# Sheet1.net
KiCad netlist of a schematic drawn in Altium Designer
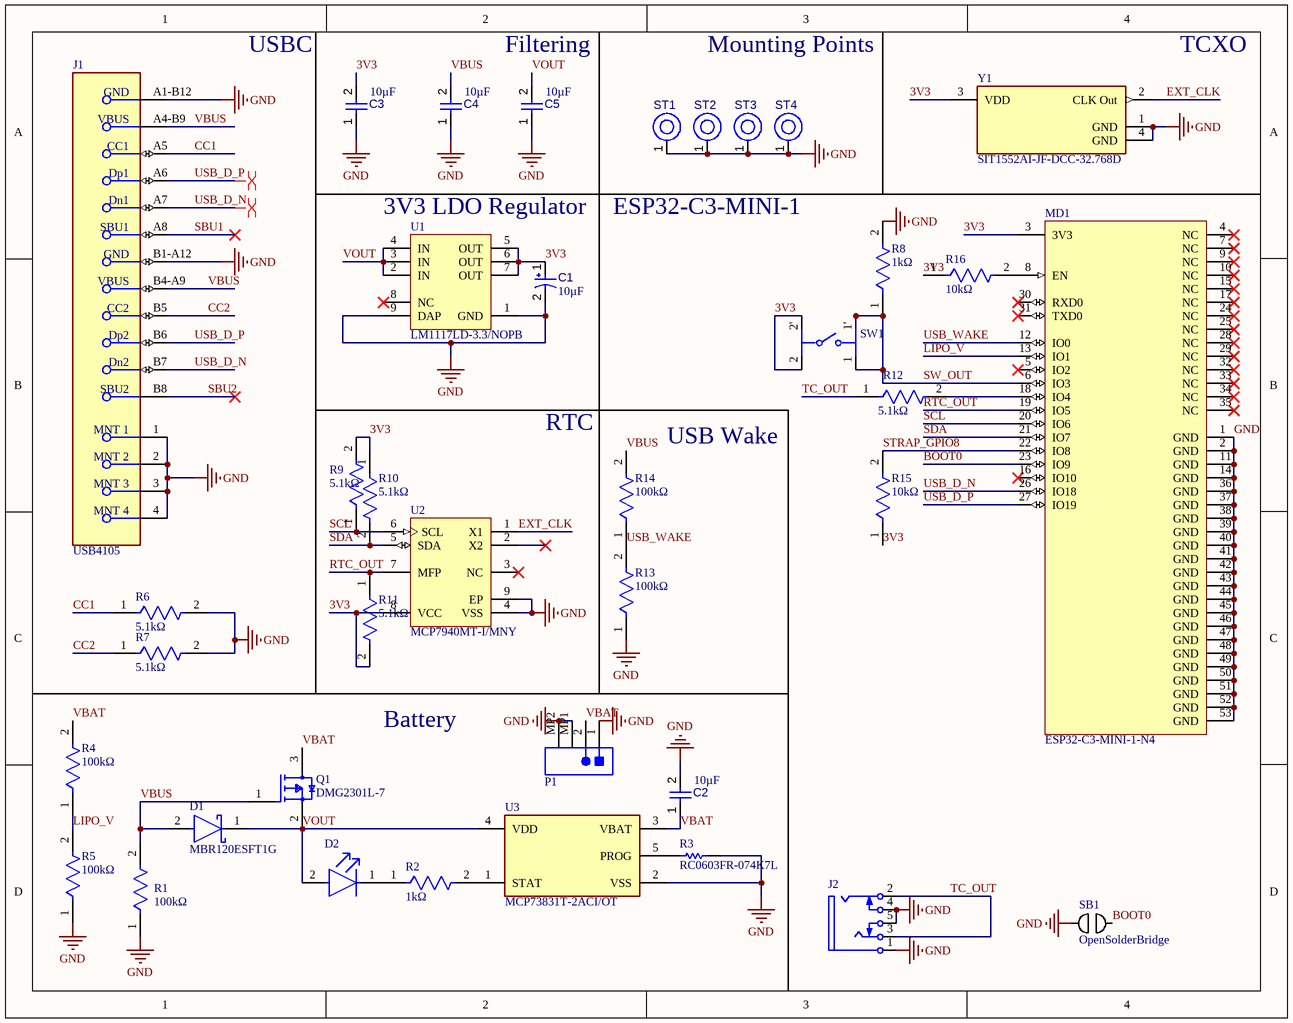
[diagram p0: Sheet1.SchDoc]

(export (version "E")
  (design (tool "Eeschema 10.0.6"))
  (components
    (comp (ref "C1")
      (value "10µF")
      (footprint "CAPMP3529X21-T_V")
      (description "Tantalum Capacitor, 10 uF, +/- 20%, 16 V, -55 to 125 degC, 1411 (3528 Metric), RoHS, Tape and Reel")
      (fields (field (name "TOLERANCE") "20%") (field (name "MANUFACTURER") "AVX Corporation"))
      (libsource (lib "Raleigh Slack") (part "CAP-P-2"))
    )
    (comp (ref "C2")
      (value "10µF")
      (footprint "CAPC0603(1608)100_L")
      (description "Chip Capacitor, 10µF +/-20%, 10V, 0603, Thickness 1 mm")
      (fields (field (name "TOLERANCE") "10%") (field (name "Comment") "Capacitor 10µF +/-20% 10V 0603"))
      (libsource (lib "Raleigh Slack") (part "CAP-NP-2"))
    )
    (comp (ref "C3")
      (value "10µF")
      (footprint "CAPC0603(1608)100_L")
      (description "Chip Capacitor, 10µF +/-20%, 10V, 0603, Thickness 1 mm")
      (fields (field (name "TOLERANCE") "10%") (field (name "Comment") "Capacitor 10µF +/-20% 10V 0603"))
      (libsource (lib "Raleigh Slack") (part "CAP-NP-2"))
    )
    (comp (ref "C4")
      (value "10µF")
      (footprint "CAPC0603(1608)100_L")
      (description "Chip Capacitor, 10µF +/-20%, 10V, 0603, Thickness 1 mm")
      (fields (field (name "TOLERANCE") "10%") (field (name "Comment") "Capacitor 10µF +/-20% 10V 0603"))
      (libsource (lib "Raleigh Slack") (part "CAP-NP-2"))
    )
    (comp (ref "C5")
      (value "10µF")
      (footprint "CAPC0603(1608)100_L")
      (description "Chip Capacitor, 10µF +/-20%, 10V, 0603, Thickness 1 mm")
      (fields (field (name "TOLERANCE") "10%") (field (name "Comment") "Capacitor 10µF +/-20% 10V 0603"))
      (libsource (lib "Raleigh Slack") (part "CAP-NP-2"))
    )
    (comp (ref "D1")
      (value "MBR120ESFT1G")
      (footprint "On_Semiconductor_498_MFG")
      (libsource (lib "Altium Content Vault") (part "MBR120ESFT1G"))
    )
    (comp (ref "D2")
      (value "VLMO1300-GS08")
      (footprint "FP-6_541-5092_01-4-MFG")
      (description "VLMO1300-GS08 LED Uni-Color Soft Orange 611nm 2-Pin Chip 0603(1608Metric) T/R")
      (libsource (lib "Altium Content Vault") (part "8706943c75ba83719d021d2fdc84c58"))
    )
    (comp (ref "J1")
      (value "USB4105")
      (footprint "FP-USB4105-GF-A-MFG")
      (description "CONN RCPT USB2.0 TYPEC 5A")
      (fields (field (name "MANUFACTURER PART NUMBER") "USB4105-GF-A") (field (name "MANUFACTURER") "GCT"))
      (libsource (lib "Altium Content Vault") (part "e7c17a616881a82b79941196b4bec10"))
    )
    (comp (ref "J2")
      (value "35RASMT4BHNTRX")
      (footprint "SWIT-35RASMT4BHNTRX_V")
      (description "Female 3.5 mm Phone Jack, 5 Position, Height 5 mm, RoHS, Tape and Reel")
      (fields (field (name "MANUFACTURER") "Switchcraft"))
      (libsource (lib "Raleigh Slack") (part "JACK-3CD5-RN"))
    )
    (comp (ref "MD1")
      (value "ESP32-C3-MINI-1-N4")
      (footprint "FP-ESP32-C3-MINI-1-N4-MFG")
      (description "Multiprotocol Modules SMD module, ESP32-C3FN4, PCB antenna, -40 C +85 C")
      (libsource (lib "Altium Content Vault") (part "ESP32-C3-MINI-1-N4"))
    )
    (comp (ref "P1")
      (value "S2B-PH-SM4-TB(LF)(SN)")
      (footprint "JST- S2B-PH-SM4-TB(LF)(SN)-2_V")
      (description "Male Header, Pitch 2 mm, 1 x 2 Position, Height 5.5 mm, -25 to 85 degC, RoHS, Tape and Reel")
      (fields (field (name "MANUFACTURER") "JST"))
      (libsource (lib "Raleigh Slack") (part "CN-1P-2M-R2"))
    )
    (comp (ref "Q1")
      (value "DMG2301L-7")
      (footprint "FP-SOT23-MFG")
      (description "MOSFET P-CH 20V 3A SOT23")
      (fields
        (field (name "MANUFACTURER") "Diodes Inc.")
        (field (name "OCTOPART") "https://octopart.com/dmg2301l-7-diodes+inc.-67250456")
      )
      (libsource (lib "Altium Content Vault") (part "b8f99f9e586195791e7fb11725ebaeb"))
    )
    (comp (ref "R1")
      (value "100kΩ")
      (footprint "FP-AC0603-MFG")
      (description "RES 100KΩ 1.00% 0.1W 0603")
      (fields (field (name "TOLERANCE") "1%"))
      (libsource (lib "Altium Content Vault") (part "1029c3af85768c4190bb7ad29bc67b5"))
    )
    (comp (ref "R2")
      (value "1kΩ")
      (footprint "FP-RC0603-0_55-IPC_C")
      (description "RES 1K OHM 1% 1/10W 0603")
      (fields (field (name "TOLERANCE") "1%"))
      (libsource (lib "Altium Content Vault") (part "1029c3af85768c4190bb7ad29bc67b5"))
    )
    (comp (ref "R3")
      (value "RC0603FR-074K7L")
      (footprint "RESC1608X55X25LL10T15")
      (description "Chip Resistor, 4.7 KOhm, +/- 1%, 0.1 W, -55 to 155 degC, 0603 (1608 Metric), RoHS, Tape and Reel")
      (fields (field (name "MANUFACTURER") "Yageo") (field (name "TOLERANCE") "1%"))
      (libsource (lib "Altium Content Vault") (part "RES-2"))
    )
    (comp (ref "R4")
      (value "100kΩ")
      (footprint "FP-AC0603-MFG")
      (description "RES 100KΩ 1.00% 0.1W 0603")
      (fields (field (name "TOLERANCE") "1%"))
      (libsource (lib "Altium Content Vault") (part "1029c3af85768c4190bb7ad29bc67b5"))
    )
    (comp (ref "R5")
      (value "100kΩ")
      (footprint "FP-AC0603-MFG")
      (description "RES 100KΩ 1.00% 0.1W 0603")
      (fields (field (name "TOLERANCE") "1%"))
      (libsource (lib "Altium Content Vault") (part "1029c3af85768c4190bb7ad29bc67b5"))
    )
    (comp (ref "R6")
      (value "5.1kΩ")
      (footprint "FP-CRCW0603-e3-IPC_C")
      (description "RES Thick Film, 5.1kΩ, 1%, 0.1W, 100ppm/°C, 0603")
      (fields (field (name "TOLERANCE") "1%"))
      (libsource (lib "Altium Content Vault") (part "1029c3af85768c4190bb7ad29bc67b5"))
    )
    (comp (ref "R7")
      (value "5.1kΩ")
      (footprint "FP-CRCW0603-e3-IPC_C")
      (description "RES Thick Film, 5.1kΩ, 1%, 0.1W, 100ppm/°C, 0603")
      (fields (field (name "TOLERANCE") "1%"))
      (libsource (lib "Altium Content Vault") (part "1029c3af85768c4190bb7ad29bc67b5"))
    )
    (comp (ref "R8")
      (value "1kΩ")
      (footprint "FP-RC0603-0_55-IPC_C")
      (description "RES 1K OHM 1% 1/10W 0603")
      (fields (field (name "TOLERANCE") "1%"))
      (libsource (lib "Altium Content Vault") (part "1029c3af85768c4190bb7ad29bc67b5"))
    )
    (comp (ref "R9")
      (value "5.1kΩ")
      (footprint "FP-CRCW0603-e3-IPC_C")
      (description "RES Thick Film, 5.1kΩ, 1%, 0.1W, 100ppm/°C, 0603")
      (fields (field (name "TOLERANCE") "1%"))
      (libsource (lib "Altium Content Vault") (part "1029c3af85768c4190bb7ad29bc67b5"))
    )
    (comp (ref "R10")
      (value "5.1kΩ")
      (footprint "FP-CRCW0603-e3-IPC_C")
      (description "RES Thick Film, 5.1kΩ, 1%, 0.1W, 100ppm/°C, 0603")
      (fields (field (name "TOLERANCE") "1%"))
      (libsource (lib "Altium Content Vault") (part "1029c3af85768c4190bb7ad29bc67b5"))
    )
    (comp (ref "R11")
      (value "5.1kΩ")
      (footprint "FP-CRCW0603-e3-IPC_C")
      (description "RES Thick Film, 5.1kΩ, 1%, 0.1W, 100ppm/°C, 0603")
      (fields (field (name "TOLERANCE") "1%"))
      (libsource (lib "Altium Content Vault") (part "1029c3af85768c4190bb7ad29bc67b5"))
    )
    (comp (ref "R12")
      (value "5.1kΩ")
      (footprint "FP-CRCW0603-e3-IPC_C")
      (description "RES Thick Film, 5.1kΩ, 1%, 0.1W, 100ppm/°C, 0603")
      (fields (field (name "TOLERANCE") "1%"))
      (libsource (lib "Altium Content Vault") (part "1029c3af85768c4190bb7ad29bc67b5"))
    )
    (comp (ref "R13")
      (value "100kΩ")
      (footprint "FP-AC0603-MFG")
      (description "RES 100KΩ 1.00% 0.1W 0603")
      (fields (field (name "TOLERANCE") "1%"))
      (libsource (lib "Altium Content Vault") (part "1029c3af85768c4190bb7ad29bc67b5"))
    )
    (comp (ref "R14")
      (value "100kΩ")
      (footprint "FP-AC0603-MFG")
      (description "RES 100KΩ 1.00% 0.1W 0603")
      (fields (field (name "TOLERANCE") "1%"))
      (libsource (lib "Altium Content Vault") (part "1029c3af85768c4190bb7ad29bc67b5"))
    )
    (comp (ref "R15")
      (value "10kΩ")
      (footprint "FP-RC0603-0_55-IPC_C")
      (description "RES 10K OHM 1% 1/10W 0603")
      (fields (field (name "TOLERANCE") "1%"))
      (libsource (lib "Altium Content Vault") (part "1029c3af85768c4190bb7ad29bc67b5"))
    )
    (comp (ref "R16")
      (value "10kΩ")
      (footprint "FP-RC0603-0_55-IPC_C")
      (description "RES 10K OHM 1% 1/10W 0603")
      (fields (field (name "TOLERANCE") "1%"))
      (libsource (lib "Altium Content Vault") (part "1029c3af85768c4190bb7ad29bc67b5"))
    )
    (comp (ref "SB1")
      (value "OpenSolderBridge")
      (footprint "OpenSolderBridge-Footprint-1")
      (libsource (lib "Raleigh Slack") (part "OpenSolderBridge"))
    )
    (comp (ref "ST1")
      (value "PTH-M2D5X5")
      (footprint "PTH-M2D5X5")
      (description "M2 PTH (2.5mm), 5mm pad")
      (libsource (lib "Raleigh Slack") (part "CMP-00028-00000-1"))
    )
    (comp (ref "ST2")
      (value "PTH-M2D5X5")
      (footprint "PTH-M2D5X5")
      (description "M2 PTH (2.5mm), 5mm pad")
      (libsource (lib "Raleigh Slack") (part "CMP-00028-00000-1"))
    )
    (comp (ref "ST3")
      (value "PTH-M2D5X5")
      (footprint "PTH-M2D5X5")
      (description "M2 PTH (2.5mm), 5mm pad")
      (libsource (lib "Raleigh Slack") (part "CMP-00028-00000-1"))
    )
    (comp (ref "ST4")
      (value "PTH-M2D5X5")
      (footprint "PTH-M2D5X5")
      (description "M2 PTH (2.5mm), 5mm pad")
      (libsource (lib "Raleigh Slack") (part "CMP-00028-00000-1"))
    )
    (comp (ref "SW1")
      (value "EVQ-9P701P")
      (footprint "FP-EVQ-9P701P-MFG")
      (description "SWITCH TACTILE SPST-NO 0.05A 12V")
      (fields
        (field (name "MANUFACTURER") "Panasonic")
        (field (name "OCTOPART") "https://octopart.com/evq-9p701p-panasonic-58006746")
      )
      (libsource (lib "Altium Content Vault") (part "67890d47754ac483cb1d3ba3be74b6c"))
    )
    (comp (ref "U1")
      (value "LM1117LD-3.3/NOPB")
      (footprint "NGN0008A_V")
      (description "800mA Low-Dropout Linear Regulator, 8-pin LLP, Pb-Free")
      (fields (field (name "MANUFACTURER") "Texas Instruments"))
      (libsource (lib "Altium Content Vault") (part "PM-REG-LM1117-IL9"))
    )
    (comp (ref "U2")
      (value "MCP7940MT-I/MNY")
      (footprint "MCHP-TDFN-MNY8_V")
      (fields (field (name "MANUFACTURER") "Microchip"))
      (libsource (lib "Altium Content Vault") (part "MCHP-MCP7940M-TDFN-8"))
    )
    (comp (ref "U3")
      (value "MCP73831T-2ACI/OT")
      (footprint "FP-C04-091-OT-IPC_B")
      (description "IC CONTROLLR LI-ION 4.2V SOT23-5")
      (libsource (lib "Altium Content Vault") (part "61f5a3bb3429d9e0caadea342aa3b19"))
    )
    (comp (ref "Y1")
      (value "SIT1552AI-JF-DCC-32.768D")
      (footprint "FP-SIT1552AI-JF-DCC-32_76-MFG")
      (description "MEMS OSC TCXO 32.7680KHZ LVCMOS")
      (libsource (lib "Altium Content Vault") (part "df761861bced6026168a8ab77df6f24"))
    )
  )
  (nets
    (net (code "1") (name "/3V3") (class "Default")
      (node (ref "C1") (pin "1") (pinfunction "1_1") (pintype "passive"))
      (node (ref "C3") (pin "2") (pinfunction "2_2") (pintype "passive"))
      (node (ref "MD1") (pin "3") (pinfunction "3V3_3") (pintype "power_in"))
      (node (ref "R10") (pin "1") (pinfunction "1_1") (pintype "passive"))
      (node (ref "R11") (pin "2") (pinfunction "2_2") (pintype "passive"))
      (node (ref "R15") (pin "1") (pinfunction "1_1") (pintype "passive"))
      (node (ref "R16") (pin "1") (pinfunction "1_1") (pintype "passive"))
      (node (ref "R9") (pin "2") (pinfunction "2_2") (pintype "passive"))
      (node (ref "SW1") (pin "2") (pinfunction "2_2") (pintype "passive"))
      (node (ref "SW1") (pin "2'") (pinfunction "2'_2'") (pintype "passive"))
      (node (ref "U1") (pin "5") (pinfunction "OUT_5") (pintype "power_in"))
      (node (ref "U1") (pin "6") (pinfunction "OUT_6") (pintype "power_in"))
      (node (ref "U1") (pin "7") (pinfunction "OUT_7") (pintype "power_in"))
      (node (ref "U2") (pin "8") (pinfunction "VCC_8") (pintype "power_in"))
      (node (ref "Y1") (pin "3") (pinfunction "VDD_3") (pintype "power_in"))
    )
    (net (code "2") (name "/BOOT0") (class "Default")
      (node (ref "MD1") (pin "23") (pinfunction "IO9_23") (pintype "bidirectional"))
      (node (ref "SB1") (pin "1") (pinfunction "1_1") (pintype "passive"))
    )
    (net (code "3") (name "/CC1") (class "Default")
      (node (ref "J1") (pin "A5") (pinfunction "CC1_A5") (pintype "bidirectional"))
      (node (ref "R6") (pin "1") (pinfunction "1_1") (pintype "passive"))
    )
    (net (code "4") (name "/CC2") (class "Default")
      (node (ref "J1") (pin "B5") (pinfunction "CC2_B5") (pintype "bidirectional"))
      (node (ref "R7") (pin "1") (pinfunction "1_1") (pintype "passive"))
    )
    (net (code "5") (name "/EXT_CLK") (class "Default")
      (node (ref "U2") (pin "1") (pinfunction "X1_1") (pintype "passive"))
      (node (ref "Y1") (pin "2") (pinfunction "CLK_Out_2") (pintype "output"))
    )
    (net (code "6") (name "/LIPO_V") (class "Default")
      (node (ref "MD1") (pin "13") (pinfunction "IO1_13") (pintype "bidirectional"))
      (node (ref "R4") (pin "1") (pinfunction "1_1") (pintype "passive"))
      (node (ref "R5") (pin "2") (pinfunction "2_2") (pintype "passive"))
    )
    (net (code "7") (name "/RTC_OUT") (class "Default")
      (node (ref "MD1") (pin "19") (pinfunction "IO5_19") (pintype "bidirectional"))
      (node (ref "R11") (pin "1") (pinfunction "1_1") (pintype "passive"))
      (node (ref "U2") (pin "7") (pinfunction "MFP_7") (pintype "open_collector"))
    )
    (net (code "8") (name "/SBU1") (class "Default")
      (node (ref "J1") (pin "A8") (pinfunction "SBU1_A8") (pintype "bidirectional+no_connect"))
    )
    (net (code "9") (name "/SBU2") (class "Default")
      (node (ref "J1") (pin "B8") (pinfunction "SBU2_B8") (pintype "power_in+no_connect"))
    )
    (net (code "10") (name "/SCL") (class "Default")
      (node (ref "MD1") (pin "20") (pinfunction "IO6_20") (pintype "bidirectional"))
      (node (ref "R9") (pin "1") (pinfunction "1_1") (pintype "passive"))
      (node (ref "U2") (pin "6") (pinfunction "SCL_6") (pintype "input"))
    )
    (net (code "11") (name "/SDA") (class "Default")
      (node (ref "MD1") (pin "21") (pinfunction "IO7_21") (pintype "bidirectional"))
      (node (ref "R10") (pin "2") (pinfunction "2_2") (pintype "passive"))
      (node (ref "U2") (pin "5") (pinfunction "SDA_5") (pintype "bidirectional"))
    )
    (net (code "12") (name "/STRAP_GPIO8") (class "Default")
      (node (ref "MD1") (pin "22") (pinfunction "IO8_22") (pintype "bidirectional"))
      (node (ref "R15") (pin "2") (pinfunction "2_2") (pintype "passive"))
    )
    (net (code "13") (name "/SW_OUT") (class "Default")
      (node (ref "MD1") (pin "6") (pinfunction "IO3_6") (pintype "bidirectional"))
      (node (ref "R8") (pin "1") (pinfunction "1_1") (pintype "passive"))
      (node (ref "SW1") (pin "1") (pinfunction "1_1") (pintype "passive"))
      (node (ref "SW1") (pin "1'") (pinfunction "1'_1'") (pintype "passive"))
    )
    (net (code "14") (name "/TC_OUT") (class "Default")
      (node (ref "J2") (pin "2") (pinfunction "2_2") (pintype "passive"))
      (node (ref "J2") (pin "3") (pinfunction "3_3") (pintype "passive"))
      (node (ref "R12") (pin "1") (pinfunction "1_1") (pintype "passive"))
    )
    (net (code "15") (name "/USB_D_N") (class "Default")
      (node (ref "J1") (pin "A7") (pinfunction "Dn1_A7") (pintype "bidirectional"))
      (node (ref "J1") (pin "B7") (pinfunction "Dn2_B7") (pintype "bidirectional"))
      (node (ref "MD1") (pin "26") (pinfunction "IO18_26") (pintype "bidirectional"))
    )
    (net (code "16") (name "/USB_D_P") (class "Default")
      (node (ref "J1") (pin "A6") (pinfunction "Dp1_A6") (pintype "bidirectional"))
      (node (ref "J1") (pin "B6") (pinfunction "Dp2_B6") (pintype "bidirectional"))
      (node (ref "MD1") (pin "27") (pinfunction "IO19_27") (pintype "bidirectional"))
    )
    (net (code "17") (name "/USB_WAKE") (class "Default")
      (node (ref "MD1") (pin "12") (pinfunction "IO0_12") (pintype "bidirectional"))
      (node (ref "R13") (pin "2") (pinfunction "2_2") (pintype "passive"))
      (node (ref "R14") (pin "1") (pinfunction "1_1") (pintype "passive"))
    )
    (net (code "18") (name "/VBAT") (class "Default")
      (node (ref "C2") (pin "1") (pinfunction "1_1") (pintype "passive"))
      (node (ref "P1") (pin "2") (pinfunction "2_2") (pintype "passive"))
      (node (ref "Q1") (pin "3") (pinfunction "D_3") (pintype "passive"))
      (node (ref "R4") (pin "2") (pinfunction "2_2") (pintype "passive"))
      (node (ref "U3") (pin "3") (pinfunction "VBAT_3") (pintype "power_in"))
    )
    (net (code "19") (name "/VBUS") (class "Default")
      (node (ref "C4") (pin "2") (pinfunction "2_2") (pintype "passive"))
      (node (ref "D1") (pin "2") (pinfunction "A_2") (pintype "passive"))
      (node (ref "J1") (pin "A4-B9") (pinfunction "VBUS_A4-B9") (pintype "power_in"))
      (node (ref "J1") (pin "B4-A9") (pinfunction "VBUS_B4-A9") (pintype "bidirectional"))
      (node (ref "Q1") (pin "1") (pinfunction "G_1") (pintype "passive"))
      (node (ref "R1") (pin "2") (pinfunction "2_2") (pintype "passive"))
      (node (ref "R14") (pin "2") (pinfunction "2_2") (pintype "passive"))
    )
    (net (code "20") (name "/VOUT") (class "Default")
      (node (ref "C5") (pin "2") (pinfunction "2_2") (pintype "passive"))
      (node (ref "D1") (pin "1") (pinfunction "C_1") (pintype "passive"))
      (node (ref "D2") (pin "2") (pinfunction "A_2") (pintype "passive"))
      (node (ref "Q1") (pin "2") (pinfunction "S_2") (pintype "passive"))
      (node (ref "U1") (pin "2") (pinfunction "IN_2") (pintype "power_in"))
      (node (ref "U1") (pin "3") (pinfunction "IN_3") (pintype "power_in"))
      (node (ref "U1") (pin "4") (pinfunction "IN_4") (pintype "power_in"))
      (node (ref "U3") (pin "4") (pinfunction "VDD_4") (pintype "power_in"))
    )
    (net (code "21") (name "GND") (class "Default")
      (node (ref "C1") (pin "2") (pinfunction "2_2") (pintype "passive"))
      (node (ref "C2") (pin "2") (pinfunction "2_2") (pintype "passive"))
      (node (ref "C3") (pin "1") (pinfunction "1_1") (pintype "passive"))
      (node (ref "C4") (pin "1") (pinfunction "1_1") (pintype "passive"))
      (node (ref "C5") (pin "1") (pinfunction "1_1") (pintype "passive"))
      (node (ref "J1") (pin "1") (pinfunction "MNT_1_1") (pintype "power_in"))
      (node (ref "J1") (pin "2") (pinfunction "MNT_2_2") (pintype "power_in"))
      (node (ref "J1") (pin "3") (pinfunction "MNT_3_3") (pintype "power_in"))
      (node (ref "J1") (pin "4") (pinfunction "MNT_4_4") (pintype "power_in"))
      (node (ref "J1") (pin "A1-B12") (pinfunction "GND_A1-B12") (pintype "power_in"))
      (node (ref "J1") (pin "B1-A12") (pinfunction "GND_B1-A12") (pintype "bidirectional"))
      (node (ref "J2") (pin "1") (pinfunction "1_1") (pintype "passive"))
      (node (ref "J2") (pin "4") (pinfunction "4_4") (pintype "passive"))
      (node (ref "J2") (pin "5") (pinfunction "5_5") (pintype "passive"))
      (node (ref "MD1") (pin "1") (pinfunction "GND_1") (pintype "power_in"))
      (node (ref "MD1") (pin "11") (pinfunction "GND_11") (pintype "power_in"))
      (node (ref "MD1") (pin "14") (pinfunction "GND_14") (pintype "power_in"))
      (node (ref "MD1") (pin "2") (pinfunction "GND_2") (pintype "power_in"))
      (node (ref "MD1") (pin "36") (pinfunction "GND_36") (pintype "power_in"))
      (node (ref "MD1") (pin "37") (pinfunction "GND_37") (pintype "power_in"))
      (node (ref "MD1") (pin "38") (pinfunction "GND_38") (pintype "power_in"))
      (node (ref "MD1") (pin "39") (pinfunction "GND_39") (pintype "power_in"))
      (node (ref "MD1") (pin "40") (pinfunction "GND_40") (pintype "power_in"))
      (node (ref "MD1") (pin "41") (pinfunction "GND_41") (pintype "power_in"))
      (node (ref "MD1") (pin "42") (pinfunction "GND_42") (pintype "power_in"))
      (node (ref "MD1") (pin "43") (pinfunction "GND_43") (pintype "power_in"))
      (node (ref "MD1") (pin "44") (pinfunction "GND_44") (pintype "power_in"))
      (node (ref "MD1") (pin "45") (pinfunction "GND_45") (pintype "power_in"))
      (node (ref "MD1") (pin "46") (pinfunction "GND_46") (pintype "power_in"))
      (node (ref "MD1") (pin "47") (pinfunction "GND_47") (pintype "power_in"))
      (node (ref "MD1") (pin "48") (pinfunction "GND_48") (pintype "power_in"))
      (node (ref "MD1") (pin "49") (pinfunction "GND_49") (pintype "power_in"))
      (node (ref "MD1") (pin "50") (pinfunction "GND_50") (pintype "power_in"))
      (node (ref "MD1") (pin "51") (pinfunction "GND_51") (pintype "power_in"))
      (node (ref "MD1") (pin "52") (pinfunction "GND_52") (pintype "power_in"))
      (node (ref "MD1") (pin "53") (pinfunction "GND_53") (pintype "power_in"))
      (node (ref "P1") (pin "1") (pinfunction "1_1") (pintype "passive"))
      (node (ref "P1") (pin "MP1") (pinfunction "MP1_MP1") (pintype "passive"))
      (node (ref "P1") (pin "MP2") (pinfunction "MP2_MP2") (pintype "passive"))
      (node (ref "R1") (pin "1") (pinfunction "1_1") (pintype "passive"))
      (node (ref "R13") (pin "1") (pinfunction "1_1") (pintype "passive"))
      (node (ref "R3") (pin "2") (pinfunction "2_2") (pintype "passive"))
      (node (ref "R5") (pin "1") (pinfunction "1_1") (pintype "passive"))
      (node (ref "R6") (pin "2") (pinfunction "2_2") (pintype "passive"))
      (node (ref "R7") (pin "2") (pinfunction "2_2") (pintype "passive"))
      (node (ref "R8") (pin "2") (pinfunction "2_2") (pintype "passive"))
      (node (ref "SB1") (pin "0") (pinfunction "0_0") (pintype "passive"))
      (node (ref "ST1") (pin "1") (pinfunction "H1_1") (pintype "passive"))
      (node (ref "ST2") (pin "1") (pinfunction "H1_1") (pintype "passive"))
      (node (ref "ST3") (pin "1") (pinfunction "H1_1") (pintype "passive"))
      (node (ref "ST4") (pin "1") (pinfunction "H1_1") (pintype "passive"))
      (node (ref "U1") (pin "1") (pinfunction "GND_1") (pintype "power_in"))
      (node (ref "U1") (pin "9") (pinfunction "DAP_9") (pintype "power_in"))
      (node (ref "U2") (pin "4") (pinfunction "VSS_4") (pintype "power_in"))
      (node (ref "U2") (pin "9") (pinfunction "EP_9") (pintype "passive"))
      (node (ref "U3") (pin "2") (pinfunction "VSS_2") (pintype "power_in"))
      (node (ref "Y1") (pin "1") (pinfunction "GND_1") (pintype "power_in"))
      (node (ref "Y1") (pin "4") (pinfunction "GND_4") (pintype "power_in"))
    )
    (net (code "22") (name "Net-(D2-C)") (class "Default")
      (node (ref "D2") (pin "1") (pinfunction "C_1") (pintype "passive"))
      (node (ref "R2") (pin "1") (pinfunction "1_1") (pintype "passive"))
    )
    (net (code "23") (name "Net-(MD1-EN)") (class "Default")
      (node (ref "MD1") (pin "8") (pinfunction "EN_8") (pintype "input"))
      (node (ref "R16") (pin "2") (pinfunction "2_2") (pintype "passive"))
    )
    (net (code "24") (name "Net-(MD1-IO4)") (class "Default")
      (node (ref "MD1") (pin "18") (pinfunction "IO4_18") (pintype "bidirectional"))
      (node (ref "R12") (pin "2") (pinfunction "2_2") (pintype "passive"))
    )
    (net (code "25") (name "Net-(U3-PROG)") (class "Default")
      (node (ref "R3") (pin "1") (pinfunction "1_1") (pintype "passive"))
      (node (ref "U3") (pin "5") (pinfunction "PROG_5") (pintype "passive"))
    )
    (net (code "26") (name "Net-(U3-STAT)") (class "Default")
      (node (ref "R2") (pin "2") (pinfunction "2_2") (pintype "passive"))
      (node (ref "U3") (pin "1") (pinfunction "STAT_1") (pintype "passive"))
    )
    (net (code "27") (name "unconnected-(MD1-IO2-Pad5)") (class "Default")
      (node (ref "MD1") (pin "5") (pinfunction "IO2_5") (pintype "bidirectional+no_connect"))
    )
    (net (code "28") (name "unconnected-(MD1-IO10-Pad16)") (class "Default")
      (node (ref "MD1") (pin "16") (pinfunction "IO10_16") (pintype "bidirectional+no_connect"))
    )
    (net (code "29") (name "unconnected-(MD1-NC-Pad4)") (class "Default")
      (node (ref "MD1") (pin "4") (pinfunction "NC_4") (pintype "passive+no_connect"))
    )
    (net (code "30") (name "unconnected-(MD1-NC-Pad7)") (class "Default")
      (node (ref "MD1") (pin "7") (pinfunction "NC_7") (pintype "passive+no_connect"))
    )
    (net (code "31") (name "unconnected-(MD1-NC-Pad9)") (class "Default")
      (node (ref "MD1") (pin "9") (pinfunction "NC_9") (pintype "passive+no_connect"))
    )
    (net (code "32") (name "unconnected-(MD1-NC-Pad10)") (class "Default")
      (node (ref "MD1") (pin "10") (pinfunction "NC_10") (pintype "passive+no_connect"))
    )
    (net (code "33") (name "unconnected-(MD1-NC-Pad15)") (class "Default")
      (node (ref "MD1") (pin "15") (pinfunction "NC_15") (pintype "passive+no_connect"))
    )
    (net (code "34") (name "unconnected-(MD1-NC-Pad17)") (class "Default")
      (node (ref "MD1") (pin "17") (pinfunction "NC_17") (pintype "passive+no_connect"))
    )
    (net (code "35") (name "unconnected-(MD1-NC-Pad24)") (class "Default")
      (node (ref "MD1") (pin "24") (pinfunction "NC_24") (pintype "passive+no_connect"))
    )
    (net (code "36") (name "unconnected-(MD1-NC-Pad25)") (class "Default")
      (node (ref "MD1") (pin "25") (pinfunction "NC_25") (pintype "passive+no_connect"))
    )
    (net (code "37") (name "unconnected-(MD1-NC-Pad28)") (class "Default")
      (node (ref "MD1") (pin "28") (pinfunction "NC_28") (pintype "passive+no_connect"))
    )
    (net (code "38") (name "unconnected-(MD1-NC-Pad29)") (class "Default")
      (node (ref "MD1") (pin "29") (pinfunction "NC_29") (pintype "passive+no_connect"))
    )
    (net (code "39") (name "unconnected-(MD1-NC-Pad32)") (class "Default")
      (node (ref "MD1") (pin "32") (pinfunction "NC_32") (pintype "passive+no_connect"))
    )
    (net (code "40") (name "unconnected-(MD1-NC-Pad33)") (class "Default")
      (node (ref "MD1") (pin "33") (pinfunction "NC_33") (pintype "passive+no_connect"))
    )
    (net (code "41") (name "unconnected-(MD1-NC-Pad34)") (class "Default")
      (node (ref "MD1") (pin "34") (pinfunction "NC_34") (pintype "passive+no_connect"))
    )
    (net (code "42") (name "unconnected-(MD1-NC-Pad35)") (class "Default")
      (node (ref "MD1") (pin "35") (pinfunction "NC_35") (pintype "passive+no_connect"))
    )
    (net (code "43") (name "unconnected-(MD1-RXD0-Pad30)") (class "Default")
      (node (ref "MD1") (pin "30") (pinfunction "RXD0_30") (pintype "bidirectional+no_connect"))
    )
    (net (code "44") (name "unconnected-(MD1-TXD0-Pad31)") (class "Default")
      (node (ref "MD1") (pin "31") (pinfunction "TXD0_31") (pintype "bidirectional+no_connect"))
    )
    (net (code "45") (name "unconnected-(U1-NC-Pad8)") (class "Default")
      (node (ref "U1") (pin "8") (pinfunction "NC_8") (pintype "passive+no_connect"))
    )
    (net (code "46") (name "unconnected-(U2-NC-Pad3)") (class "Default")
      (node (ref "U2") (pin "3") (pinfunction "NC_3") (pintype "passive+no_connect"))
    )
    (net (code "47") (name "unconnected-(U2-X2-Pad2)") (class "Default")
      (node (ref "U2") (pin "2") (pinfunction "X2_2") (pintype "passive+no_connect"))
    )
  )
)
